# Coco2Composite.net
KiCad netlist of a schematic drawn in EAGLE
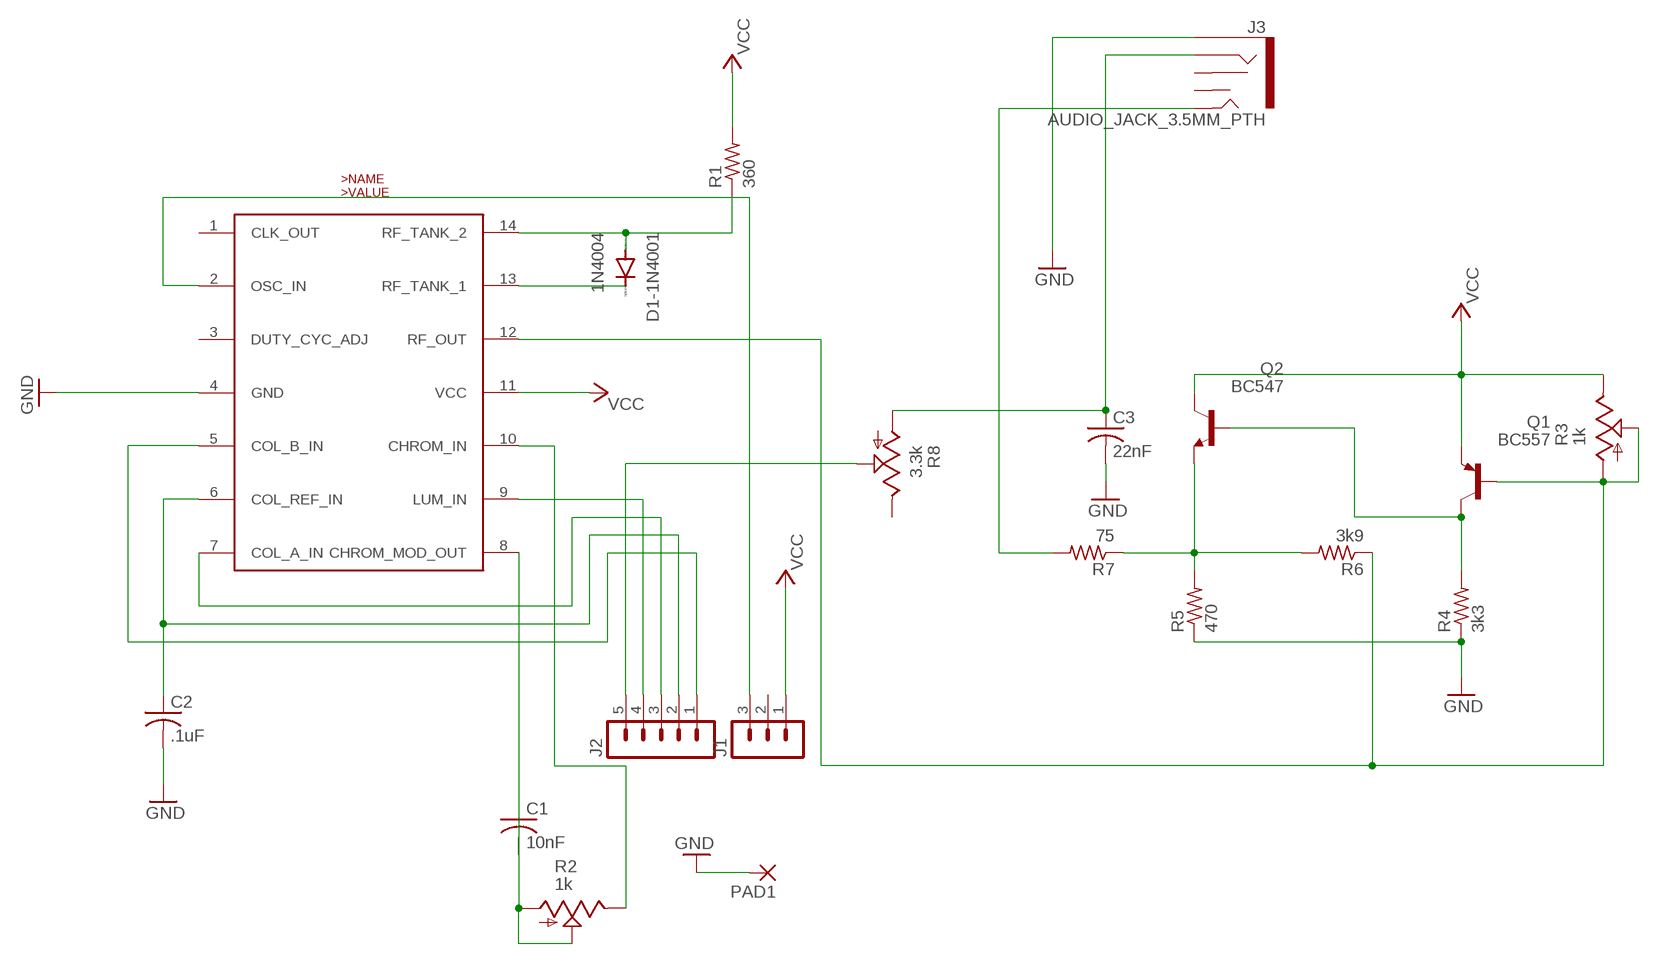
[diagram p0: schematic, sheet 1]

(export (version "E")
  (design (tool "Eeschema 10.0.6"))
  (components
    (comp (ref "C1")
      (value "10nF")
      (footprint "eagle-import:C025-024X044")
      (libsource (lib "eagle-import") (part "C-US025-024X044"))
    )
    (comp (ref "C2")
      (value ".1uF")
      (footprint "eagle-import:C025-024X044")
      (libsource (lib "eagle-import") (part "C-US025-024X044"))
    )
    (comp (ref "C3")
      (value "22nF")
      (footprint "eagle-import:C025-024X044")
      (libsource (lib "eagle-import") (part "C-US025-024X044"))
    )
    (comp (ref "D1-1N4001")
      (value "1N4004")
      (footprint "eagle-import:DO41-10")
      (libsource (lib "eagle-import") (part "1N4004"))
    )
    (comp (ref "J1")
      (value "MA03-1")
      (footprint "eagle-import:MA03-1")
      (libsource (lib "eagle-import") (part "MA03-1"))
    )
    (comp (ref "J2")
      (value "MA05-1")
      (footprint "eagle-import:MA05-1")
      (libsource (lib "eagle-import") (part "MA05-1"))
    )
    (comp (ref "J3")
      (value "AUDIO_JACK_3.5MM_PTH")
      (footprint "eagle-import:AUDIO-JACK")
      (libsource (lib "eagle-import") (part "AUDIO_JACK_3.5MM_PTH"))
    )
    (comp (ref "PAD1")
      (value "2,54/0,8")
      (footprint "eagle-import:2,54_0,8")
      (libsource (lib "eagle-import") (part "2,54/0,8"))
    )
    (comp (ref "Q1")
      (value "BC557")
      (footprint "eagle-import:TO92-EBC")
      (libsource (lib "eagle-import") (part "BC557"))
    )
    (comp (ref "Q2")
      (value "BC547")
      (footprint "eagle-import:TO92")
      (libsource (lib "eagle-import") (part "BC547"))
    )
    (comp (ref "R1")
      (value "360")
      (footprint "eagle-import:0204V")
      (libsource (lib "eagle-import") (part "R-US_0204/2V"))
    )
    (comp (ref "R2")
      (value "1k")
      (footprint "eagle-import:B25U")
      (libsource (lib "eagle-import") (part "TRIM_US-B25U"))
    )
    (comp (ref "R3")
      (value "1k")
      (footprint "eagle-import:B25U")
      (libsource (lib "eagle-import") (part "TRIM_US-B25U"))
    )
    (comp (ref "R4")
      (value "3k3")
      (footprint "eagle-import:0204V")
      (libsource (lib "eagle-import") (part "R-US_0204/2V"))
    )
    (comp (ref "R5")
      (value "470")
      (footprint "eagle-import:0204V")
      (libsource (lib "eagle-import") (part "R-US_0204/2V"))
    )
    (comp (ref "R6")
      (value "3k9")
      (footprint "eagle-import:0204V")
      (libsource (lib "eagle-import") (part "R-US_0204/2V"))
    )
    (comp (ref "R7")
      (value "75")
      (footprint "eagle-import:0204V")
      (libsource (lib "eagle-import") (part "R-US_0204/2V"))
    )
    (comp (ref "R8")
      (value "3.3k")
      (footprint "eagle-import:B25U")
      (libsource (lib "eagle-import") (part "TRIM_US-B25U"))
    )
    (comp (ref "U1")
      (value "MC1372")
      (footprint "eagle-import:DIP14")
      (libsource (lib "eagle-import") (part "MC1372"))
    )
  )
  (nets
    (net (code "1") (name "GND") (class "Default")
      (node (ref "C2") (pin "2") (pinfunction "2_2") (pintype "passive"))
      (node (ref "C3") (pin "2") (pinfunction "2_2") (pintype "passive"))
      (node (ref "J3") (pin "SLEEVE") (pinfunction "SLEEVE_SLEEVE") (pintype "bidirectional"))
      (node (ref "PAD1") (pin "1") (pinfunction "P_1") (pintype "passive"))
      (node (ref "R4") (pin "1") (pinfunction "1_1") (pintype "passive"))
      (node (ref "R5") (pin "1") (pinfunction "1_1") (pintype "passive"))
      (node (ref "U1") (pin "4") (pinfunction "GND_4") (pintype "bidirectional"))
    )
    (net (code "2") (name "Net-(C1-Pad1)") (class "Default")
      (node (ref "C1") (pin "1") (pinfunction "1_1") (pintype "passive"))
      (node (ref "R2") (pin "A") (pinfunction "A_A") (pintype "passive"))
      (node (ref "R2") (pin "S") (pinfunction "S_S") (pintype "passive"))
    )
    (net (code "3") (name "Net-(C3-Pad1)") (class "Default")
      (node (ref "C3") (pin "1") (pinfunction "1_1") (pintype "passive"))
      (node (ref "J3") (pin "RING") (pinfunction "RING_RING") (pintype "bidirectional"))
      (node (ref "R8") (pin "A") (pinfunction "A_A") (pintype "passive"))
    )
    (net (code "4") (name "Net-(J2-Pad5)") (class "Default")
      (node (ref "J2") (pin "5") (pinfunction "5_5") (pintype "passive"))
      (node (ref "R8") (pin "S") (pinfunction "S_S") (pintype "passive"))
    )
    (net (code "5") (name "Net-(J3-PadTIP)") (class "Default")
      (node (ref "J3") (pin "TIP") (pinfunction "TIP_TIP") (pintype "bidirectional"))
      (node (ref "R7") (pin "2") (pinfunction "2_2") (pintype "passive"))
    )
    (net (code "6") (name "Net-(Q2-B)") (class "Default")
      (node (ref "Q1") (pin "C") (pinfunction "C_C") (pintype "passive"))
      (node (ref "Q2") (pin "2") (pinfunction "B_2") (pintype "passive"))
      (node (ref "R4") (pin "2") (pinfunction "2_2") (pintype "passive"))
    )
    (net (code "7") (name "Net-(Q2-E)") (class "Default")
      (node (ref "Q2") (pin "1") (pinfunction "E_1") (pintype "passive"))
      (node (ref "R5") (pin "2") (pinfunction "2_2") (pintype "passive"))
      (node (ref "R6") (pin "2") (pinfunction "2_2") (pintype "passive"))
      (node (ref "R7") (pin "1") (pinfunction "1_1") (pintype "passive"))
    )
    (net (code "8") (name "Net-(U1-CHROM_IN)") (class "Default")
      (node (ref "R2") (pin "E") (pinfunction "E_E") (pintype "passive"))
      (node (ref "U1") (pin "10") (pinfunction "CHROM_IN_10") (pintype "bidirectional"))
    )
    (net (code "9") (name "Net-(U1-CHROM_MOD_OUT)") (class "Default")
      (node (ref "C1") (pin "2") (pinfunction "2_2") (pintype "passive"))
      (node (ref "U1") (pin "8") (pinfunction "CHROM_MOD_OUT_8") (pintype "bidirectional"))
    )
    (net (code "10") (name "Net-(U1-COL_A_IN)") (class "Default")
      (node (ref "J2") (pin "3") (pinfunction "3_3") (pintype "passive"))
      (node (ref "U1") (pin "7") (pinfunction "COL_A_IN_7") (pintype "bidirectional"))
    )
    (net (code "11") (name "Net-(U1-COL_B_IN)") (class "Default")
      (node (ref "J2") (pin "1") (pinfunction "1_1") (pintype "passive"))
      (node (ref "U1") (pin "5") (pinfunction "COL_B_IN_5") (pintype "bidirectional"))
    )
    (net (code "12") (name "Net-(U1-COL_REF_IN)") (class "Default")
      (node (ref "C2") (pin "1") (pinfunction "1_1") (pintype "passive"))
      (node (ref "J2") (pin "2") (pinfunction "2_2") (pintype "passive"))
      (node (ref "U1") (pin "6") (pinfunction "COL_REF_IN_6") (pintype "bidirectional"))
    )
    (net (code "13") (name "Net-(U1-LUM_IN)") (class "Default")
      (node (ref "J2") (pin "4") (pinfunction "4_4") (pintype "passive"))
      (node (ref "U1") (pin "9") (pinfunction "LUM_IN_9") (pintype "bidirectional"))
    )
    (net (code "14") (name "Net-(U1-OSC_IN)") (class "Default")
      (node (ref "J1") (pin "3") (pinfunction "3_3") (pintype "passive"))
      (node (ref "U1") (pin "2") (pinfunction "OSC_IN_2") (pintype "bidirectional"))
    )
    (net (code "15") (name "Net-(U1-RF_OUT)") (class "Default")
      (node (ref "Q1") (pin "B") (pinfunction "B_B") (pintype "passive"))
      (node (ref "R3") (pin "A") (pinfunction "A_A") (pintype "passive"))
      (node (ref "R3") (pin "S") (pinfunction "S_S") (pintype "passive"))
      (node (ref "R6") (pin "1") (pinfunction "1_1") (pintype "passive"))
      (node (ref "U1") (pin "12") (pinfunction "RF_OUT_12") (pintype "bidirectional"))
    )
    (net (code "16") (name "Net-(U1-RF_TANK_1)") (class "Default")
      (node (ref "D1-1N4001") (pin "C") (pinfunction "C_C") (pintype "passive"))
      (node (ref "U1") (pin "13") (pinfunction "RF_TANK_1_13") (pintype "bidirectional"))
    )
    (net (code "17") (name "Net-(U1-RF_TANK_2)") (class "Default")
      (node (ref "D1-1N4001") (pin "A") (pinfunction "A_A") (pintype "passive"))
      (node (ref "R1") (pin "1") (pinfunction "1_1") (pintype "passive"))
      (node (ref "U1") (pin "14") (pinfunction "RF_TANK_2_14") (pintype "bidirectional"))
    )
    (net (code "18") (name "VCC") (class "Default")
      (node (ref "J1") (pin "1") (pinfunction "1_1") (pintype "passive"))
      (node (ref "Q1") (pin "E") (pinfunction "E_E") (pintype "passive"))
      (node (ref "Q2") (pin "3") (pinfunction "C_3") (pintype "passive"))
      (node (ref "R1") (pin "2") (pinfunction "2_2") (pintype "passive"))
      (node (ref "R3") (pin "E") (pinfunction "E_E") (pintype "passive"))
      (node (ref "U1") (pin "11") (pinfunction "VCC_11") (pintype "bidirectional"))
    )
    (net (code "19") (name "unconnected-(J1-Pad2)") (class "Default")
      (node (ref "J1") (pin "2") (pinfunction "2_2") (pintype "passive"))
    )
    (net (code "20") (name "unconnected-(J3-PadRSH)") (class "Default")
      (node (ref "J3") (pin "RSH") (pinfunction "RSH_RSH") (pintype "bidirectional"))
    )
    (net (code "21") (name "unconnected-(J3-PadTSH)") (class "Default")
      (node (ref "J3") (pin "TSH") (pinfunction "TSH_TSH") (pintype "bidirectional"))
    )
    (net (code "22") (name "unconnected-(R8-PadE)") (class "Default")
      (node (ref "R8") (pin "E") (pinfunction "E_E") (pintype "passive"))
    )
    (net (code "23") (name "unconnected-(U1-CLK_OUT-Pad1)") (class "Default")
      (node (ref "U1") (pin "1") (pinfunction "CLK_OUT_1") (pintype "bidirectional"))
    )
    (net (code "24") (name "unconnected-(U1-DUTY_CYC_ADJ-Pad3)") (class "Default")
      (node (ref "U1") (pin "3") (pinfunction "DUTY_CYC_ADJ_3") (pintype "bidirectional"))
    )
  )
)
